# FPC-ETH-DualRJ45.net
KiCad netlist of a schematic drawn in Altium Designer
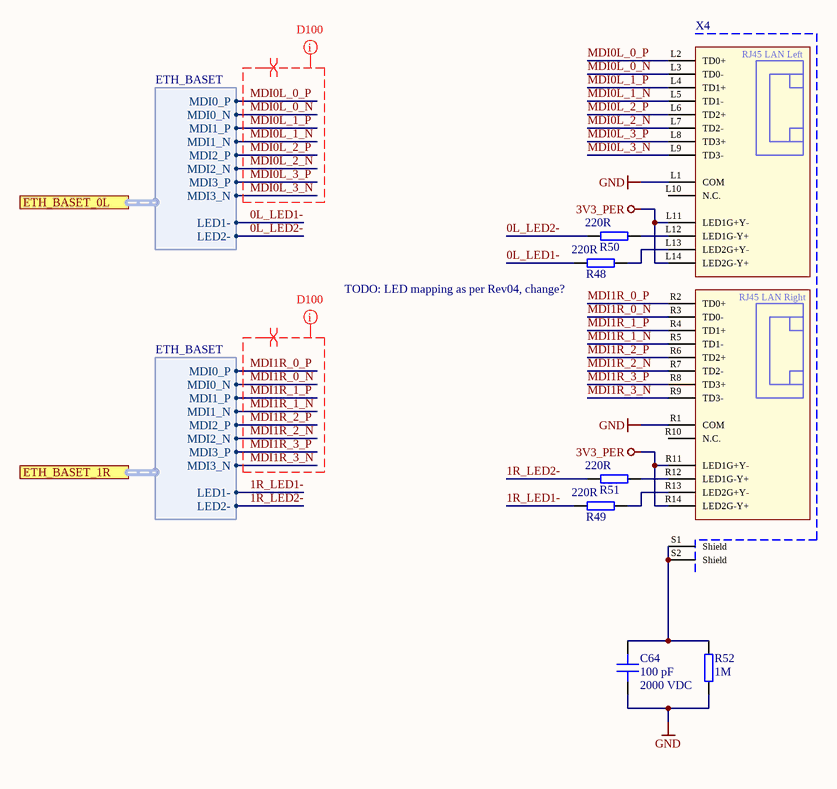
[diagram p0: FPC-ETH-DualRJ45.SchDoc]

(export (version "E")
  (design (tool "Eeschema 10.0.6"))
  (components
    (comp (ref "C64")
      (value "100 pF")
      (footprint "C_1206_TE")
      (description "2kV 100pF NP0 ±5% 1206 Multilayer Ceramic Capacitors MLCC - SMD/SMT ROHS")
      (fields
        (field (name "MANUFACTURER PART NUMBER") "CC1206JKNPODBN101")
        (field (name "MANUFACTURER") "YAGEO")
        (field (name "VOLTAGE RATING") "2000 VDC")
        (field (name "CREATED FROM") "AGeiger")
      )
      (libsource (lib "user") (part "Capacitor"))
    )
    (comp (ref "R48")
      (value "220R")
      (footprint "R_0603_TE")
      (description "Generic resistor")
      (fields
        (field (name "MANUFACTURER PART NUMBER") "UZgen_R_0603_220R")
        (field (name "MANUFACTURER") "UZgen")
        (field (name "CREATED FROM") "UZgenTool")
      )
      (libsource (lib "user") (part "RES"))
    )
    (comp (ref "R49")
      (value "220R")
      (footprint "R_0603_TE")
      (description "Generic resistor")
      (fields
        (field (name "MANUFACTURER PART NUMBER") "UZgen_R_0603_220R")
        (field (name "MANUFACTURER") "UZgen")
        (field (name "CREATED FROM") "UZgenTool")
      )
      (libsource (lib "user") (part "RES"))
    )
    (comp (ref "R50")
      (value "220R")
      (footprint "R_0603_TE")
      (description "Generic resistor")
      (fields
        (field (name "MANUFACTURER PART NUMBER") "UZgen_R_0603_220R")
        (field (name "MANUFACTURER") "UZgen")
        (field (name "CREATED FROM") "UZgenTool")
      )
      (libsource (lib "user") (part "RES"))
    )
    (comp (ref "R51")
      (value "220R")
      (footprint "R_0603_TE")
      (description "Generic resistor")
      (fields
        (field (name "MANUFACTURER PART NUMBER") "UZgen_R_0603_220R")
        (field (name "MANUFACTURER") "UZgen")
        (field (name "CREATED FROM") "UZgenTool")
      )
      (libsource (lib "user") (part "RES"))
    )
    (comp (ref "R52")
      (value "1M")
      (footprint "RES 1206_3216")
      (fields
        (field (name "MANUFACTURER PART NUMBER") "1206W4F1004T5E")
        (field (name "MANUFACTURER") "UNI-ROYAL")
        (field (name "TOLERANCE") "1%")
        (field (name "CREATED FROM") "AGeiger")
      )
      (libsource (lib "user") (part "Resistor"))
    )
    (comp (ref "X4")
      (value "~")
      (footprint "74991214400")
      (fields
        (field (name "MANUFACTURER PART NUMBER") "74991214400")
        (field (name "MANUFACTURER") "Würth Elektronik")
        (field (name "LCSC PART NUMBER") "C29641821")
        (field (name "CREATED FROM") "MGeier")
      )
      (libsource (lib "user") (part "74991214400"))
    )
  )
  (nets
    (net (code "2") (name "/0L_LED1-") (class "Default")
      (node (ref "R48") (pin "1") (pinfunction "1_1") (pintype "passive"))
    )
    (net (code "3") (name "/0L_LED2-") (class "Default")
      (node (ref "R50") (pin "1") (pinfunction "1_1") (pintype "passive"))
    )
    (net (code "4") (name "/1R_LED1-") (class "Default")
      (node (ref "R49") (pin "1") (pinfunction "1_1") (pintype "passive"))
    )
    (net (code "5") (name "/1R_LED2-") (class "Default")
      (node (ref "R51") (pin "1") (pinfunction "1_1") (pintype "passive"))
    )
    (net (code "6") (name "/MDI0L_0_N") (class "Default")
      (node (ref "X4") (pin "L3") (pinfunction "TD0-_L3") (pintype "passive"))
    )
    (net (code "7") (name "/MDI0L_0_P") (class "Default")
      (node (ref "X4") (pin "L2") (pinfunction "TD0+_L2") (pintype "passive"))
    )
    (net (code "8") (name "/MDI0L_1_N") (class "Default")
      (node (ref "X4") (pin "L5") (pinfunction "TD1-_L5") (pintype "passive"))
    )
    (net (code "9") (name "/MDI0L_1_P") (class "Default")
      (node (ref "X4") (pin "L4") (pinfunction "TD1+_L4") (pintype "passive"))
    )
    (net (code "10") (name "/MDI0L_2_N") (class "Default")
      (node (ref "X4") (pin "L7") (pinfunction "TD2-_L7") (pintype "passive"))
    )
    (net (code "11") (name "/MDI0L_2_P") (class "Default")
      (node (ref "X4") (pin "L6") (pinfunction "TD2+_L6") (pintype "passive"))
    )
    (net (code "12") (name "/MDI0L_3_N") (class "Default")
      (node (ref "X4") (pin "L9") (pinfunction "TD3-_L9") (pintype "passive"))
    )
    (net (code "13") (name "/MDI0L_3_P") (class "Default")
      (node (ref "X4") (pin "L8") (pinfunction "TD3+_L8") (pintype "passive"))
    )
    (net (code "14") (name "/MDI1R_0_N") (class "Default")
      (node (ref "X4") (pin "R3") (pinfunction "TD0-_R3") (pintype "passive"))
    )
    (net (code "15") (name "/MDI1R_0_P") (class "Default")
      (node (ref "X4") (pin "R2") (pinfunction "TD0+_R2") (pintype "passive"))
    )
    (net (code "16") (name "/MDI1R_1_N") (class "Default")
      (node (ref "X4") (pin "R5") (pinfunction "TD1-_R5") (pintype "passive"))
    )
    (net (code "17") (name "/MDI1R_1_P") (class "Default")
      (node (ref "X4") (pin "R4") (pinfunction "TD1+_R4") (pintype "passive"))
    )
    (net (code "18") (name "/MDI1R_2_N") (class "Default")
      (node (ref "X4") (pin "R7") (pinfunction "TD2-_R7") (pintype "passive"))
    )
    (net (code "19") (name "/MDI1R_2_P") (class "Default")
      (node (ref "X4") (pin "R6") (pinfunction "TD2+_R6") (pintype "passive"))
    )
    (net (code "20") (name "/MDI1R_3_N") (class "Default")
      (node (ref "X4") (pin "R9") (pinfunction "TD3-_R9") (pintype "passive"))
    )
    (net (code "21") (name "/MDI1R_3_P") (class "Default")
      (node (ref "X4") (pin "R8") (pinfunction "TD3+_R8") (pintype "passive"))
    )
    (net (code "23") (name "3V3_PER") (class "Default")
      (node (ref "X4") (pin "L11") (pinfunction "LED1G+Y-_L11") (pintype "passive"))
      (node (ref "X4") (pin "L14") (pinfunction "LED2G-Y+_L14") (pintype "passive"))
      (node (ref "X4") (pin "R11") (pinfunction "LED1G+Y-_R11") (pintype "passive"))
      (node (ref "X4") (pin "R14") (pinfunction "LED2G-Y+_R14") (pintype "passive"))
    )
    (net (code "24") (name "GND") (class "Default")
      (node (ref "C64") (pin "1") (pinfunction "1_1") (pintype "passive"))
      (node (ref "R52") (pin "1") (pinfunction "1_1") (pintype "passive"))
      (node (ref "X4") (pin "L1") (pinfunction "COM_L1") (pintype "passive"))
      (node (ref "X4") (pin "R1") (pinfunction "COM_R1") (pintype "passive"))
    )
    (net (code "25") (name "Net-(C64-Pad2)") (class "Default")
      (node (ref "C64") (pin "2") (pinfunction "2_2") (pintype "passive"))
      (node (ref "R52") (pin "2") (pinfunction "2_2") (pintype "passive"))
      (node (ref "X4") (pin "S1") (pinfunction "Shield_S1") (pintype "passive"))
      (node (ref "X4") (pin "S2") (pinfunction "Shield_S2") (pintype "passive"))
    )
    (net (code "26") (name "Net-(R48-Pad2)") (class "Default")
      (node (ref "R48") (pin "2") (pinfunction "2_2") (pintype "passive"))
      (node (ref "X4") (pin "L13") (pinfunction "LED2G+Y-_L13") (pintype "passive"))
    )
    (net (code "27") (name "Net-(R49-Pad2)") (class "Default")
      (node (ref "R49") (pin "2") (pinfunction "2_2") (pintype "passive"))
      (node (ref "X4") (pin "R13") (pinfunction "LED2G+Y-_R13") (pintype "passive"))
    )
    (net (code "28") (name "Net-(R50-Pad2)") (class "Default")
      (node (ref "R50") (pin "2") (pinfunction "2_2") (pintype "passive"))
      (node (ref "X4") (pin "L12") (pinfunction "LED1G-Y+_L12") (pintype "passive"))
    )
    (net (code "29") (name "Net-(R51-Pad2)") (class "Default")
      (node (ref "R51") (pin "2") (pinfunction "2_2") (pintype "passive"))
      (node (ref "X4") (pin "R12") (pinfunction "LED1G-Y+_R12") (pintype "passive"))
    )
    (net (code "30") (name "unconnected-(X4-N.C.-PadL10)") (class "Default")
      (node (ref "X4") (pin "L10") (pinfunction "N.C._L10") (pintype "passive"))
    )
    (net (code "31") (name "unconnected-(X4-N.C.-PadR10)") (class "Default")
      (node (ref "X4") (pin "R10") (pinfunction "N.C._R10") (pintype "passive"))
    )
  )
)
